# button_switch.net
KiCad netlist of a schematic drawn in EAGLE
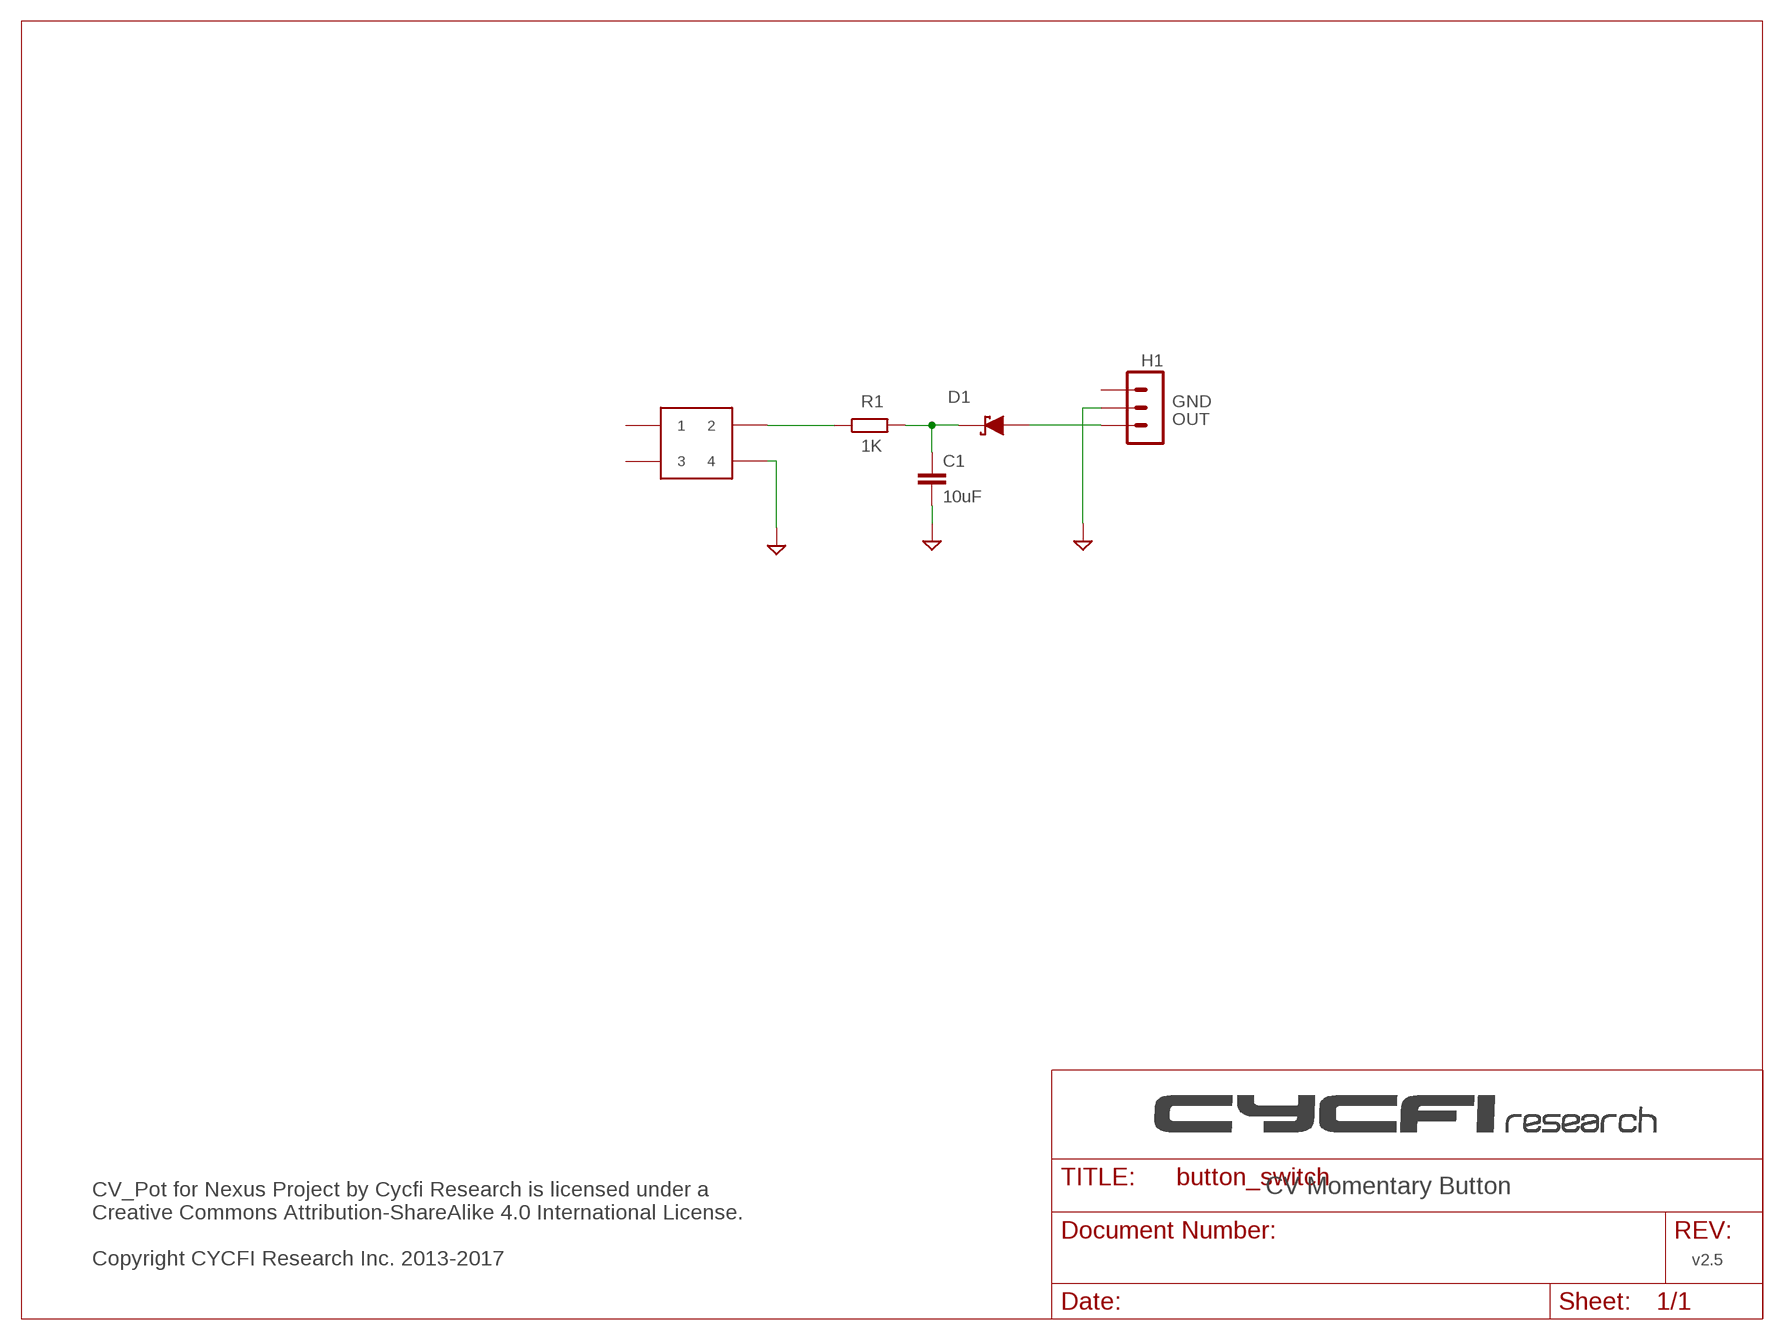
[diagram p0: schematic, sheet 1]

(export (version "E")
  (design (tool "Eeschema 10.0.6"))
  (components
    (comp (ref "C1")
      (value "10uF")
      (footprint "eagle-import:C0603")
      (libsource (lib "eagle-import") (part "C-EUC0603"))
    )
    (comp (ref "D1")
      (value "D_SCHOTTKYL")
      (footprint "eagle-import:SOD-323")
      (libsource (lib "eagle-import") (part "D_SCHOTTKYL"))
    )
    (comp (ref "H1")
      (value "3PIN-SMD-2.54MM")
      (footprint "eagle-import:3P-SMD-2.54MM")
      (libsource (lib "eagle-import") (part "3PIN-SMD-2.54MM"))
    )
    (comp (ref "R1")
      (value "1K")
      (footprint "eagle-import:R0402")
      (libsource (lib "eagle-import") (part "R-EU_R0402"))
    )
    (comp (ref "U$1")
      (value "TACT_6X6_SMD")
      (footprint "eagle-import:TACT_6X6_SMD")
      (libsource (lib "eagle-import") (part "TACT_6X6_SMD"))
    )
  )
  (nets
    (net (code "1") (name "GND") (class "Default")
      (node (ref "C1") (pin "2") (pinfunction "2_2") (pintype "passive"))
      (node (ref "H1") (pin "P$2") (pinfunction "2_P$2") (pintype "passive"))
      (node (ref "U$1") (pin "P$4") (pinfunction "4_P$4") (pintype "bidirectional"))
    )
    (net (code "2") (name "Net-(D1-A)") (class "Default")
      (node (ref "D1") (pin "1") (pinfunction "A_1") (pintype "passive"))
      (node (ref "H1") (pin "P$1") (pinfunction "1_P$1") (pintype "passive"))
    )
    (net (code "3") (name "Net-(D1-C)") (class "Default")
      (node (ref "C1") (pin "1") (pinfunction "1_1") (pintype "passive"))
      (node (ref "D1") (pin "2") (pinfunction "C_2") (pintype "passive"))
      (node (ref "R1") (pin "2") (pinfunction "2_2") (pintype "passive"))
    )
    (net (code "4") (name "Net-(U$1-2)") (class "Default")
      (node (ref "R1") (pin "1") (pinfunction "1_1") (pintype "passive"))
      (node (ref "U$1") (pin "P$2") (pinfunction "2_P$2") (pintype "bidirectional"))
    )
    (net (code "5") (name "unconnected-(H1-3-PadP$3)") (class "Default")
      (node (ref "H1") (pin "P$3") (pinfunction "3_P$3") (pintype "passive"))
    )
    (net (code "6") (name "unconnected-(U$1-1-PadP$1)") (class "Default")
      (node (ref "U$1") (pin "P$1") (pinfunction "1_P$1") (pintype "bidirectional"))
    )
    (net (code "7") (name "unconnected-(U$1-3-PadP$3)") (class "Default")
      (node (ref "U$1") (pin "P$3") (pinfunction "3_P$3") (pintype "bidirectional"))
    )
  )
)
